# 2020.net
KiCad netlist of a schematic drawn in Altium Designer
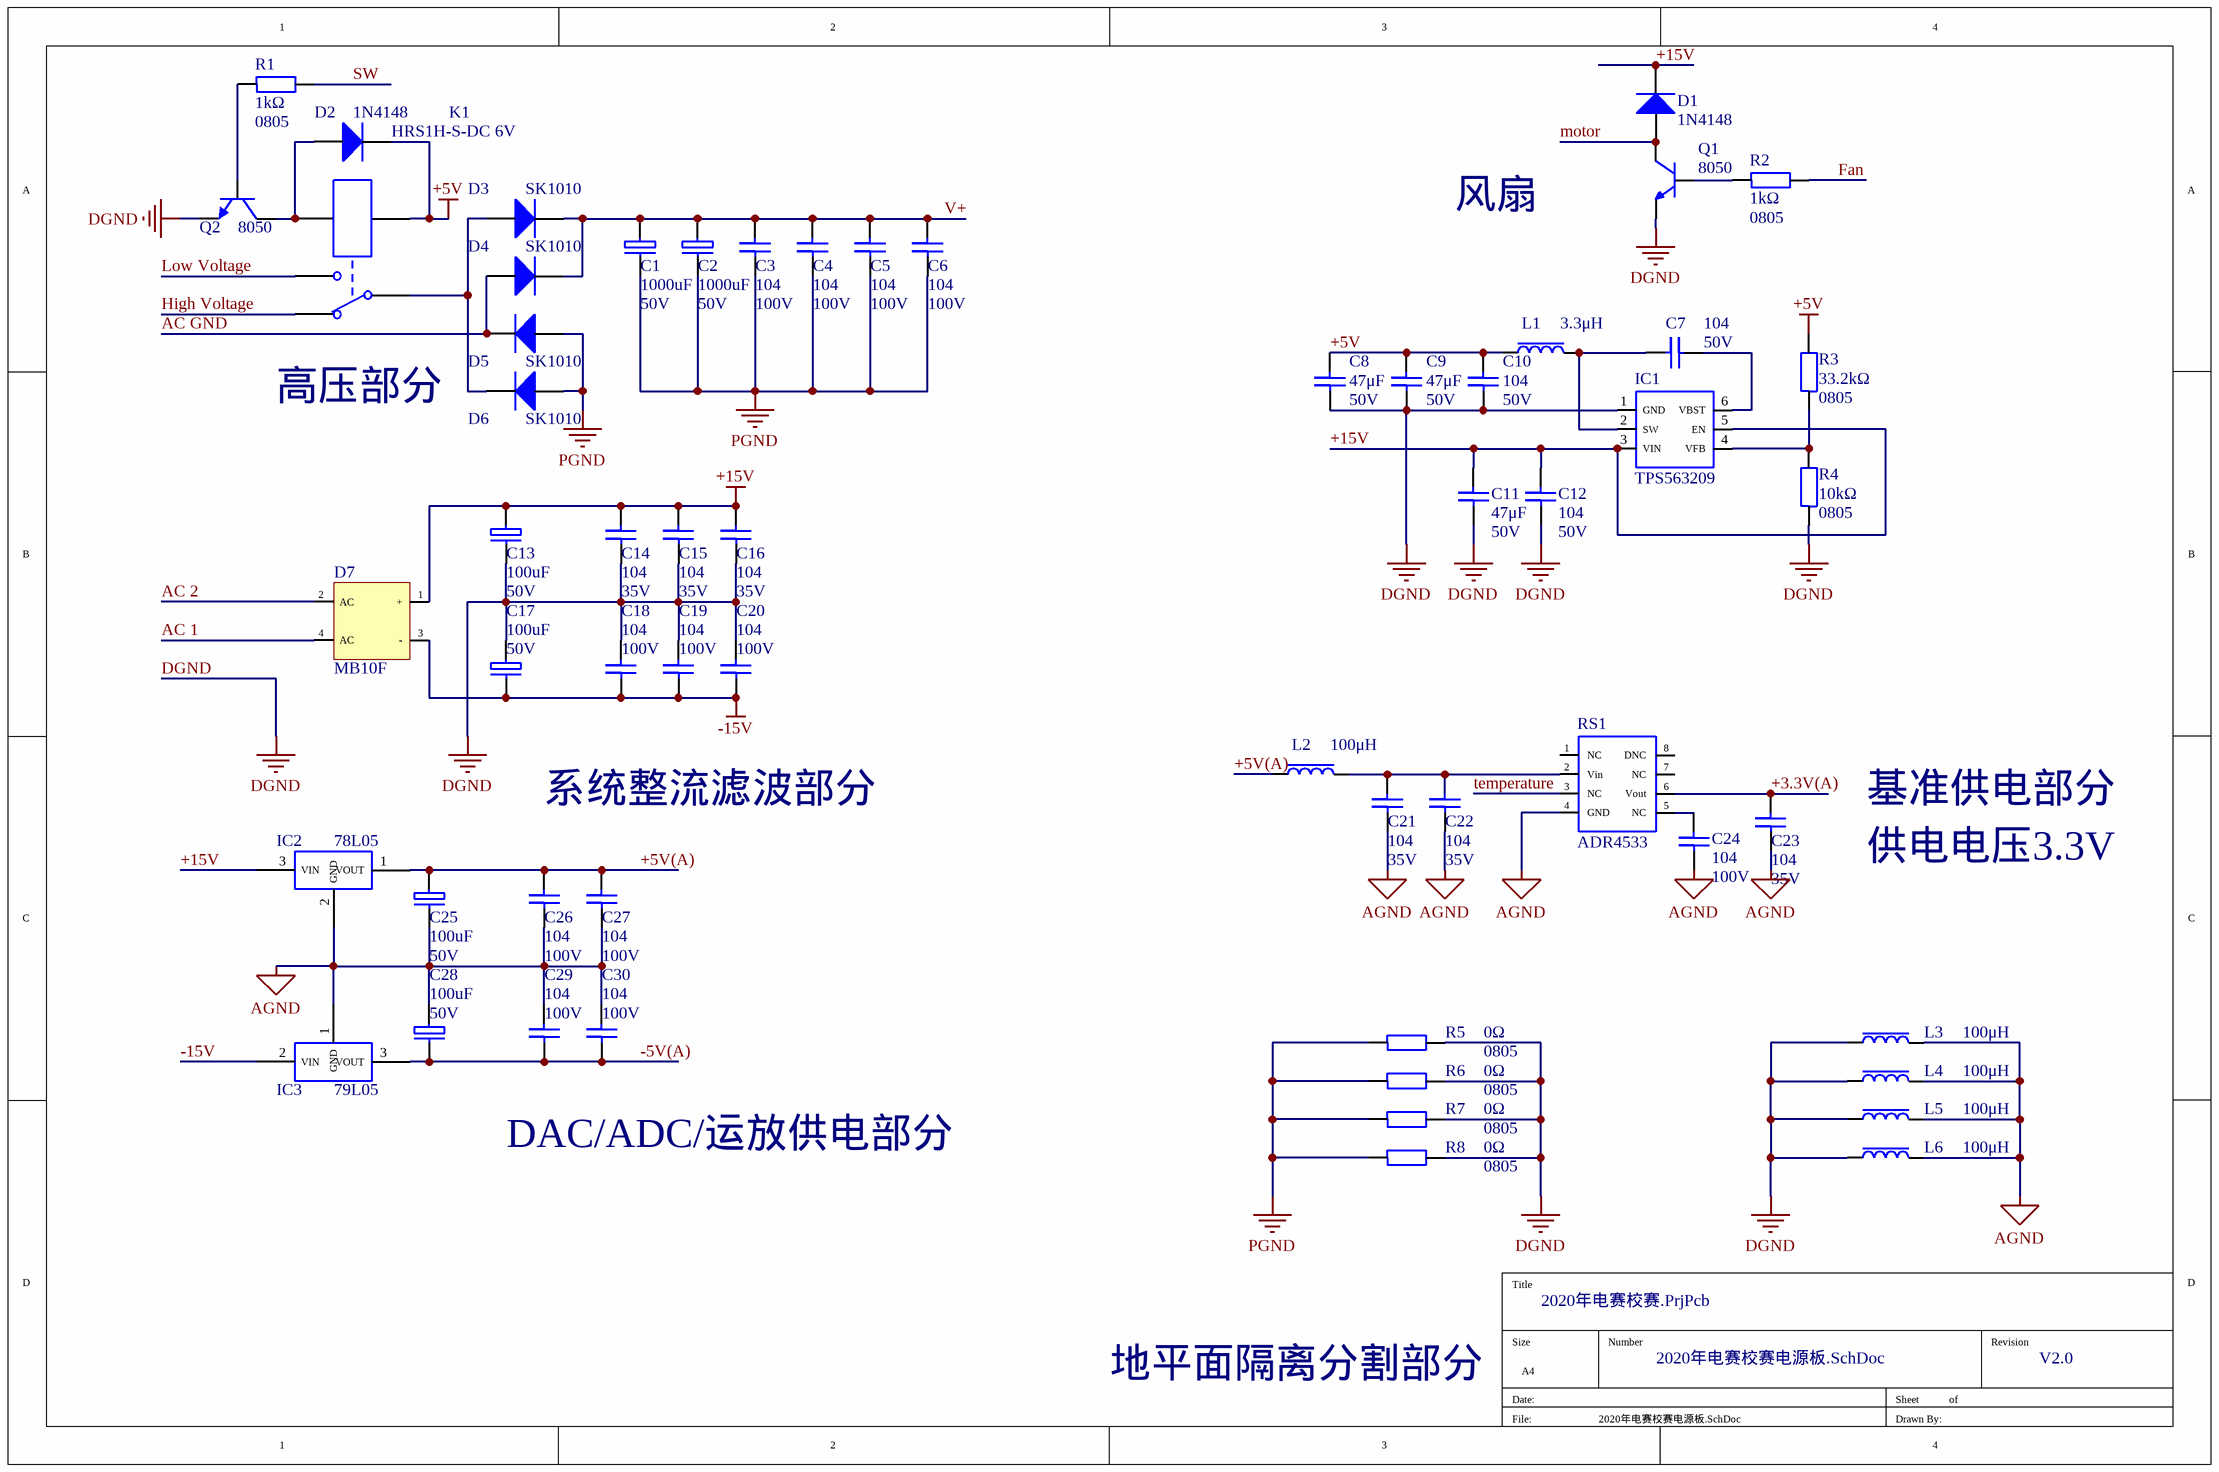
[diagram p0: 2020年电赛校赛电源板.SchDoc]

(export (version "E")
  (design (tool "Eeschema 10.0.6"))
  (components
    (comp (ref "C1")
      (value "1000uF")
      (footprint "50V 1000uF")
      (description "有极性电容")
      (fields (field (name "ALTIUM_VALUE") "50V"))
      (libsource (lib "原理图库") (part "100uF"))
    )
    (comp (ref "C2")
      (value "1000uF")
      (footprint "50V 1000uF")
      (description "有极性电容")
      (fields (field (name "ALTIUM_VALUE") "50V"))
      (libsource (lib "原理图库") (part "100uF"))
    )
    (comp (ref "C3")
      (value "104")
      (footprint "C0805")
      (description "无极性电容")
      (fields (field (name "ALTIUM_VALUE") "100V"))
      (libsource (lib "原理图库") (part "104"))
    )
    (comp (ref "C4")
      (value "104")
      (footprint "C0805")
      (description "无极性电容")
      (fields (field (name "ALTIUM_VALUE") "100V"))
      (libsource (lib "原理图库") (part "104"))
    )
    (comp (ref "C5")
      (value "104")
      (footprint "C0805")
      (description "无极性电容")
      (fields (field (name "ALTIUM_VALUE") "100V"))
      (libsource (lib "原理图库") (part "104"))
    )
    (comp (ref "C6")
      (value "104")
      (footprint "C0805")
      (description "无极性电容")
      (fields (field (name "ALTIUM_VALUE") "100V"))
      (libsource (lib "原理图库") (part "104"))
    )
    (comp (ref "C7")
      (value "104")
      (footprint "C0805")
      (description "无极性电容")
      (fields (field (name "ALTIUM_VALUE") "50V"))
      (libsource (lib "原理图库") (part "104"))
    )
    (comp (ref "C8")
      (value "47μF")
      (footprint "C1210")
      (description "无极性电容")
      (fields (field (name "ALTIUM_VALUE") "50V"))
      (libsource (lib "原理图库") (part "104"))
    )
    (comp (ref "C9")
      (value "47μF")
      (footprint "C1210")
      (description "无极性电容")
      (fields (field (name "ALTIUM_VALUE") "50V"))
      (libsource (lib "原理图库") (part "104"))
    )
    (comp (ref "C10")
      (value "104")
      (footprint "C0805")
      (description "无极性电容")
      (fields (field (name "ALTIUM_VALUE") "50V"))
      (libsource (lib "原理图库") (part "104"))
    )
    (comp (ref "C11")
      (value "47μF")
      (footprint "C1210")
      (description "无极性电容")
      (fields (field (name "ALTIUM_VALUE") "50V"))
      (libsource (lib "原理图库") (part "104"))
    )
    (comp (ref "C12")
      (value "104")
      (footprint "C0805")
      (description "无极性电容")
      (fields (field (name "ALTIUM_VALUE") "50V"))
      (libsource (lib "原理图库") (part "104"))
    )
    (comp (ref "C13")
      (value "100uF")
      (footprint "35V 470uF")
      (description "有极性电容")
      (fields (field (name "ALTIUM_VALUE") "50V"))
      (libsource (lib "原理图库") (part "100uF"))
    )
    (comp (ref "C14")
      (value "104")
      (footprint "C0805")
      (description "无极性电容")
      (fields (field (name "ALTIUM_VALUE") "35V"))
      (libsource (lib "原理图库") (part "104"))
    )
    (comp (ref "C15")
      (value "104")
      (footprint "C0805")
      (description "无极性电容")
      (fields (field (name "ALTIUM_VALUE") "35V"))
      (libsource (lib "原理图库") (part "104"))
    )
    (comp (ref "C16")
      (value "104")
      (footprint "C0805")
      (description "无极性电容")
      (fields (field (name "ALTIUM_VALUE") "35V"))
      (libsource (lib "原理图库") (part "104"))
    )
    (comp (ref "C17")
      (value "100uF")
      (footprint "35V 470uF")
      (description "有极性电容")
      (fields (field (name "ALTIUM_VALUE") "50V"))
      (libsource (lib "原理图库") (part "100uF"))
    )
    (comp (ref "C18")
      (value "104")
      (footprint "C0805")
      (description "无极性电容")
      (fields (field (name "ALTIUM_VALUE") "100V"))
      (libsource (lib "原理图库") (part "104"))
    )
    (comp (ref "C19")
      (value "104")
      (footprint "C0805")
      (description "无极性电容")
      (fields (field (name "ALTIUM_VALUE") "100V"))
      (libsource (lib "原理图库") (part "104"))
    )
    (comp (ref "C20")
      (value "104")
      (footprint "C0805")
      (description "无极性电容")
      (fields (field (name "ALTIUM_VALUE") "100V"))
      (libsource (lib "原理图库") (part "104"))
    )
    (comp (ref "C21")
      (value "104")
      (footprint "C0805")
      (description "无极性电容")
      (fields (field (name "ALTIUM_VALUE") "35V"))
      (libsource (lib "原理图库") (part "104"))
    )
    (comp (ref "C22")
      (value "104")
      (footprint "C0805")
      (description "无极性电容")
      (fields (field (name "ALTIUM_VALUE") "35V"))
      (libsource (lib "原理图库") (part "104"))
    )
    (comp (ref "C23")
      (value "104")
      (footprint "C0805")
      (description "无极性电容")
      (fields (field (name "ALTIUM_VALUE") "35V"))
      (libsource (lib "原理图库") (part "104"))
    )
    (comp (ref "C24")
      (value "104")
      (footprint "C0805")
      (description "无极性电容")
      (fields (field (name "ALTIUM_VALUE") "100V"))
      (libsource (lib "原理图库") (part "104"))
    )
    (comp (ref "C25")
      (value "100uF")
      (footprint "35V 470uF")
      (description "有极性电容")
      (fields (field (name "ALTIUM_VALUE") "50V"))
      (libsource (lib "原理图库") (part "100uF"))
    )
    (comp (ref "C26")
      (value "104")
      (footprint "C0805")
      (description "无极性电容")
      (fields (field (name "ALTIUM_VALUE") "100V"))
      (libsource (lib "原理图库") (part "104"))
    )
    (comp (ref "C27")
      (value "104")
      (footprint "C0805")
      (description "无极性电容")
      (fields (field (name "ALTIUM_VALUE") "100V"))
      (libsource (lib "原理图库") (part "104"))
    )
    (comp (ref "C28")
      (value "100uF")
      (footprint "35V 470uF")
      (description "有极性电容")
      (fields (field (name "ALTIUM_VALUE") "50V"))
      (libsource (lib "原理图库") (part "100uF"))
    )
    (comp (ref "C29")
      (value "104")
      (footprint "C0805")
      (description "无极性电容")
      (fields (field (name "ALTIUM_VALUE") "100V"))
      (libsource (lib "原理图库") (part "104"))
    )
    (comp (ref "C30")
      (value "104")
      (footprint "C0805")
      (description "无极性电容")
      (fields (field (name "ALTIUM_VALUE") "100V"))
      (libsource (lib "原理图库") (part "104"))
    )
    (comp (ref "D1")
      (value "1N4148")
      (footprint "LL34")
      (description "二极管")
      (libsource (lib "原理图库") (part "Diode"))
    )
    (comp (ref "D2")
      (value "1N4148")
      (footprint "LL34")
      (description "二极管")
      (libsource (lib "原理图库") (part "Diode"))
    )
    (comp (ref "D3")
      (value "SK1010")
      (footprint "SMC(DO-214AB)")
      (description "二极管")
      (libsource (lib "原理图库") (part "Diode"))
    )
    (comp (ref "D4")
      (value "SK1010")
      (footprint "SMC(DO-214AB)")
      (description "二极管")
      (libsource (lib "原理图库") (part "Diode"))
    )
    (comp (ref "D5")
      (value "SK1010")
      (footprint "SMC(DO-214AB)")
      (description "二极管")
      (libsource (lib "原理图库") (part "Diode"))
    )
    (comp (ref "D6")
      (value "SK1010")
      (footprint "SMC(DO-214AB)")
      (description "二极管")
      (libsource (lib "原理图库") (part "Diode"))
    )
    (comp (ref "D7")
      (value "MB10F")
      (footprint "整流桥 SMD")
      (description "1A 1000V整流桥")
      (libsource (lib "原理图库") (part "MB10F"))
    )
    (comp (ref "IC1")
      (value "TPS563209")
      (footprint "TSOP-6")
      (description "buck型电源管理")
      (libsource (lib "原理图库") (part "TPS563209/563309"))
    )
    (comp (ref "IC2")
      (value "78L05")
      (footprint "SOT-89")
      (description "LDO")
      (libsource (lib "原理图库") (part "AMS1117-3.3"))
    )
    (comp (ref "IC3")
      (value "79L05")
      (footprint "SOT-89")
      (description "LDO")
      (libsource (lib "原理图库") (part "790?"))
    )
    (comp (ref "K1")
      (value "HRS1H-S-DC 6V")
      (footprint "HRS1H-S-DC 6V")
      (description "继电器")
      (libsource (lib "原理图库") (part "HRS1H-S-DC 6V"))
    )
    (comp (ref "L1")
      (value "3.3μH")
      (footprint "L0630")
      (description "电感")
      (libsource (lib "原理图库") (part "470mH"))
    )
    (comp (ref "L2")
      (value "100μH")
      (footprint "R0805")
      (description "电感")
      (libsource (lib "原理图库") (part "470mH"))
    )
    (comp (ref "L3")
      (value "100μH")
      (footprint "R0805")
      (description "电感")
      (libsource (lib "原理图库") (part "470mH"))
    )
    (comp (ref "L4")
      (value "100μH")
      (footprint "R0805")
      (description "电感")
      (libsource (lib "原理图库") (part "470mH"))
    )
    (comp (ref "L5")
      (value "100μH")
      (footprint "R0805")
      (description "电感")
      (libsource (lib "原理图库") (part "470mH"))
    )
    (comp (ref "L6")
      (value "100μH")
      (footprint "R0805")
      (description "电感")
      (libsource (lib "原理图库") (part "470mH"))
    )
    (comp (ref "Q1")
      (value "8050")
      (footprint "SOT-23")
      (description "三极管")
      (libsource (lib "原理图库") (part "NPN!"))
    )
    (comp (ref "Q2")
      (value "8050")
      (footprint "SOT-23")
      (description "三极管")
      (libsource (lib "原理图库") (part "NPN"))
    )
    (comp (ref "R1")
      (value "1kΩ")
      (footprint "R0805")
      (description "贴片/直插电阻")
      (fields (field (name "ALTIUM_VALUE") "0805"))
      (libsource (lib "原理图库") (part "10kΩ"))
    )
    (comp (ref "R2")
      (value "1kΩ")
      (footprint "R0805")
      (description "贴片/直插电阻")
      (fields (field (name "ALTIUM_VALUE") "0805"))
      (libsource (lib "原理图库") (part "10kΩ"))
    )
    (comp (ref "R3")
      (value "33.2kΩ")
      (footprint "R0805")
      (description "贴片/直插电阻")
      (fields (field (name "ALTIUM_VALUE") "0805"))
      (libsource (lib "原理图库") (part "10kΩ"))
    )
    (comp (ref "R4")
      (value "10kΩ")
      (footprint "R0805")
      (description "贴片/直插电阻")
      (fields (field (name "ALTIUM_VALUE") "0805"))
      (libsource (lib "原理图库") (part "10kΩ"))
    )
    (comp (ref "R5")
      (value "0Ω")
      (footprint "R0805")
      (description "贴片/直插电阻")
      (fields (field (name "ALTIUM_VALUE") "0805"))
      (libsource (lib "原理图库") (part "10kΩ"))
    )
    (comp (ref "R6")
      (value "0Ω")
      (footprint "R0805")
      (description "贴片/直插电阻")
      (fields (field (name "ALTIUM_VALUE") "0805"))
      (libsource (lib "原理图库") (part "10kΩ"))
    )
    (comp (ref "R7")
      (value "0Ω")
      (footprint "R0805")
      (description "贴片/直插电阻")
      (fields (field (name "ALTIUM_VALUE") "0805"))
      (libsource (lib "原理图库") (part "10kΩ"))
    )
    (comp (ref "R8")
      (value "0Ω")
      (footprint "R0805")
      (description "贴片/直插电阻")
      (fields (field (name "ALTIUM_VALUE") "0805"))
      (libsource (lib "原理图库") (part "10kΩ"))
    )
    (comp (ref "RS1")
      (value "ADR4533")
      (footprint "SOP-8(体宽3.8mm)")
      (description "高精度基准源")
      (libsource (lib "原理图库") (part "ADR4533"))
    )
  )
  (nets
    (net (code "1") (name "+5V") (class "Default")
      (node (ref "C10") (pin "2") (pintype "passive"))
      (node (ref "C8") (pin "2") (pintype "passive"))
      (node (ref "C9") (pin "2") (pintype "passive"))
      (node (ref "D2") (pin "2") (pinfunction "K_2") (pintype "passive"))
      (node (ref "K1") (pin "2") (pinfunction "2_2") (pintype "passive"))
      (node (ref "L1") (pin "2") (pintype "passive"))
      (node (ref "R3") (pin "2") (pintype "passive"))
    )
    (net (code "2") (name "+15V") (class "Default")
      (node (ref "C11") (pin "2") (pintype "passive"))
      (node (ref "C12") (pin "2") (pintype "passive"))
      (node (ref "C13") (pin "1") (pinfunction "+_1") (pintype "passive"))
      (node (ref "C14") (pin "2") (pintype "passive"))
      (node (ref "C15") (pin "2") (pintype "passive"))
      (node (ref "C16") (pin "2") (pintype "passive"))
      (node (ref "D1") (pin "2") (pinfunction "K_2") (pintype "passive"))
      (node (ref "D7") (pin "1") (pinfunction "+_1") (pintype "passive"))
      (node (ref "IC1") (pin "3") (pinfunction "VIN_3") (pintype "passive"))
      (node (ref "IC1") (pin "5") (pinfunction "EN_5") (pintype "passive"))
      (node (ref "IC2") (pin "3") (pinfunction "VIN_3") (pintype "power_in"))
    )
    (net (code "3") (name "-15V") (class "Default")
      (node (ref "C17") (pin "2") (pinfunction "-_2") (pintype "passive"))
      (node (ref "C18") (pin "1") (pintype "passive"))
      (node (ref "C19") (pin "1") (pintype "passive"))
      (node (ref "C20") (pin "1") (pintype "passive"))
      (node (ref "D7") (pin "3") (pinfunction "-_3") (pintype "passive"))
      (node (ref "IC3") (pin "2") (pinfunction "VIN_2") (pintype "power_in"))
    )
    (net (code "4") (name "/+3.3V(A)") (class "Default")
      (node (ref "C23") (pin "2") (pintype "passive"))
      (node (ref "RS1") (pin "6") (pinfunction "Vout_6") (pintype "passive"))
    )
    (net (code "5") (name "/+5V(A)") (class "Default")
      (node (ref "C25") (pin "1") (pinfunction "+_1") (pintype "passive"))
      (node (ref "C26") (pin "2") (pintype "passive"))
      (node (ref "C27") (pin "2") (pintype "passive"))
      (node (ref "IC2") (pin "1") (pinfunction "VOUT_1") (pintype "power_in"))
      (node (ref "L2") (pin "2") (pintype "passive"))
    )
    (net (code "6") (name "/-5V(A)") (class "Default")
      (node (ref "C28") (pin "2") (pinfunction "-_2") (pintype "passive"))
      (node (ref "C29") (pin "1") (pintype "passive"))
      (node (ref "C30") (pin "1") (pintype "passive"))
      (node (ref "IC3") (pin "3") (pinfunction "VOUT_3") (pintype "power_in"))
    )
    (net (code "7") (name "/AC 1") (class "Default")
      (node (ref "D7") (pin "4") (pinfunction "AC_4") (pintype "passive"))
    )
    (net (code "8") (name "/AC 2") (class "Default")
      (node (ref "D7") (pin "2") (pinfunction "AC_2") (pintype "passive"))
    )
    (net (code "9") (name "/AC GND") (class "Default")
      (node (ref "D4") (pin "1") (pinfunction "A_1") (pintype "passive"))
      (node (ref "D5") (pin "2") (pinfunction "K_2") (pintype "passive"))
    )
    (net (code "10") (name "/Fan") (class "Default") (node (ref "R2") (pin "2") (pintype "passive")))
    (net (code "11") (name "/High Voltage") (class "Default")
      (node (ref "K1") (pin "1") (pinfunction "1_1") (pintype "passive"))
    )
    (net (code "12") (name "/Low Voltage") (class "Default")
      (node (ref "K1") (pin "6") (pinfunction "6_6") (pintype "passive"))
    )
    (net (code "13") (name "/SW") (class "Default") (node (ref "R1") (pin "2") (pintype "passive")))
    (net (code "14") (name "/V+") (class "Default")
      (node (ref "C1") (pin "1") (pinfunction "+_1") (pintype "passive"))
      (node (ref "C2") (pin "1") (pinfunction "+_1") (pintype "passive"))
      (node (ref "C3") (pin "2") (pintype "passive"))
      (node (ref "C4") (pin "2") (pintype "passive"))
      (node (ref "C5") (pin "2") (pintype "passive"))
      (node (ref "C6") (pin "2") (pintype "passive"))
      (node (ref "D3") (pin "2") (pinfunction "K_2") (pintype "passive"))
      (node (ref "D4") (pin "2") (pinfunction "K_2") (pintype "passive"))
    )
    (net (code "15") (name "/motor") (class "Default")
      (node (ref "D1") (pin "1") (pinfunction "A_1") (pintype "passive"))
      (node (ref "Q1") (pin "3") (pinfunction "C_3") (pintype "passive"))
    )
    (net (code "16") (name "/temperature") (class "Default")
      (node (ref "RS1") (pin "3") (pinfunction "NC_3") (pintype "passive"))
    )
    (net (code "17") (name "AGND") (class "Default")
      (node (ref "C21") (pin "1") (pintype "passive"))
      (node (ref "C22") (pin "1") (pintype "passive"))
      (node (ref "C23") (pin "1") (pintype "passive"))
      (node (ref "C24") (pin "1") (pintype "passive"))
      (node (ref "C25") (pin "2") (pinfunction "-_2") (pintype "passive"))
      (node (ref "C26") (pin "1") (pintype "passive"))
      (node (ref "C27") (pin "1") (pintype "passive"))
      (node (ref "C28") (pin "1") (pinfunction "+_1") (pintype "passive"))
      (node (ref "C29") (pin "2") (pintype "passive"))
      (node (ref "C30") (pin "2") (pintype "passive"))
      (node (ref "IC2") (pin "2") (pinfunction "GND_2") (pintype "passive"))
      (node (ref "IC3") (pin "1") (pinfunction "GND_1") (pintype "passive"))
      (node (ref "L3") (pin "1") (pintype "passive"))
      (node (ref "L4") (pin "1") (pintype "passive"))
      (node (ref "L5") (pin "1") (pintype "passive"))
      (node (ref "L6") (pin "1") (pintype "passive"))
      (node (ref "RS1") (pin "4") (pinfunction "GND_4") (pintype "passive"))
    )
    (net (code "18") (name "DGND") (class "Default")
      (node (ref "C10") (pin "1") (pintype "passive"))
      (node (ref "C11") (pin "1") (pintype "passive"))
      (node (ref "C12") (pin "1") (pintype "passive"))
      (node (ref "C13") (pin "2") (pinfunction "-_2") (pintype "passive"))
      (node (ref "C14") (pin "1") (pintype "passive"))
      (node (ref "C15") (pin "1") (pintype "passive"))
      (node (ref "C16") (pin "1") (pintype "passive"))
      (node (ref "C17") (pin "1") (pinfunction "+_1") (pintype "passive"))
      (node (ref "C18") (pin "2") (pintype "passive"))
      (node (ref "C19") (pin "2") (pintype "passive"))
      (node (ref "C20") (pin "2") (pintype "passive"))
      (node (ref "C8") (pin "1") (pintype "passive"))
      (node (ref "C9") (pin "1") (pintype "passive"))
      (node (ref "IC1") (pin "1") (pinfunction "GND_1") (pintype "passive"))
      (node (ref "L3") (pin "2") (pintype "passive"))
      (node (ref "L4") (pin "2") (pintype "passive"))
      (node (ref "L5") (pin "2") (pintype "passive"))
      (node (ref "L6") (pin "2") (pintype "passive"))
      (node (ref "Q1") (pin "2") (pinfunction "E_2") (pintype "passive"))
      (node (ref "Q2") (pin "2") (pinfunction "E_2") (pintype "passive"))
      (node (ref "R4") (pin "1") (pintype "passive"))
      (node (ref "R5") (pin "2") (pintype "passive"))
      (node (ref "R6") (pin "2") (pintype "passive"))
      (node (ref "R7") (pin "2") (pintype "passive"))
      (node (ref "R8") (pin "2") (pintype "passive"))
    )
    (net (code "19") (name "Net-(C24-Pad2)") (class "Default")
      (node (ref "C24") (pin "2") (pintype "passive"))
      (node (ref "RS1") (pin "5") (pinfunction "NC_5") (pintype "passive"))
    )
    (net (code "20") (name "Net-(D2-A)") (class "Default")
      (node (ref "D2") (pin "1") (pinfunction "A_1") (pintype "passive"))
      (node (ref "K1") (pin "5") (pinfunction "5_5") (pintype "passive"))
      (node (ref "Q2") (pin "3") (pinfunction "C_3") (pintype "passive"))
    )
    (net (code "21") (name "Net-(D3-A)") (class "Default")
      (node (ref "D3") (pin "1") (pinfunction "A_1") (pintype "passive"))
      (node (ref "D6") (pin "2") (pinfunction "K_2") (pintype "passive"))
      (node (ref "K1") (pin "4") (pinfunction "4_4") (pintype "passive"))
    )
    (net (code "22") (name "Net-(IC1-SW)") (class "Default")
      (node (ref "C7") (pin "1") (pintype "passive"))
      (node (ref "IC1") (pin "2") (pinfunction "SW_2") (pintype "passive"))
      (node (ref "L1") (pin "1") (pintype "passive"))
    )
    (net (code "23") (name "Net-(IC1-VBST)") (class "Default")
      (node (ref "C7") (pin "2") (pintype "passive"))
      (node (ref "IC1") (pin "6") (pinfunction "VBST_6") (pintype "passive"))
    )
    (net (code "24") (name "Net-(IC1-VFB)") (class "Default")
      (node (ref "IC1") (pin "4") (pinfunction "VFB_4") (pintype "passive"))
      (node (ref "R3") (pin "1") (pintype "passive"))
      (node (ref "R4") (pin "2") (pintype "passive"))
    )
    (net (code "25") (name "Net-(Q1-B)") (class "Default")
      (node (ref "Q1") (pin "1") (pinfunction "B_1") (pintype "passive"))
      (node (ref "R2") (pin "1") (pintype "passive"))
    )
    (net (code "26") (name "Net-(Q2-B)") (class "Default")
      (node (ref "Q2") (pin "1") (pinfunction "B_1") (pintype "passive"))
      (node (ref "R1") (pin "1") (pintype "passive"))
    )
    (net (code "27") (name "Net-(RS1-Vin)") (class "Default")
      (node (ref "C21") (pin "2") (pintype "passive"))
      (node (ref "C22") (pin "2") (pintype "passive"))
      (node (ref "L2") (pin "1") (pintype "passive"))
      (node (ref "RS1") (pin "2") (pinfunction "Vin_2") (pintype "passive"))
    )
    (net (code "28") (name "PGND") (class "Default")
      (node (ref "C1") (pin "2") (pinfunction "-_2") (pintype "passive"))
      (node (ref "C2") (pin "2") (pinfunction "-_2") (pintype "passive"))
      (node (ref "C3") (pin "1") (pintype "passive"))
      (node (ref "C4") (pin "1") (pintype "passive"))
      (node (ref "C5") (pin "1") (pintype "passive"))
      (node (ref "C6") (pin "1") (pintype "passive"))
      (node (ref "D5") (pin "1") (pinfunction "A_1") (pintype "passive"))
      (node (ref "D6") (pin "1") (pinfunction "A_1") (pintype "passive"))
      (node (ref "R5") (pin "1") (pintype "passive"))
      (node (ref "R6") (pin "1") (pintype "passive"))
      (node (ref "R7") (pin "1") (pintype "passive"))
      (node (ref "R8") (pin "1") (pintype "passive"))
    )
    (net (code "29") (name "unconnected-(RS1-DNC-Pad8)") (class "Default")
      (node (ref "RS1") (pin "8") (pinfunction "DNC_8") (pintype "passive"))
    )
    (net (code "30") (name "unconnected-(RS1-NC-Pad1)") (class "Default")
      (node (ref "RS1") (pin "1") (pinfunction "NC_1") (pintype "passive"))
    )
    (net (code "31") (name "unconnected-(RS1-NC-Pad7)") (class "Default")
      (node (ref "RS1") (pin "7") (pinfunction "NC_7") (pintype "passive"))
    )
  )
)
